# Sch.net
KiCad netlist of a schematic drawn in Altium Designer
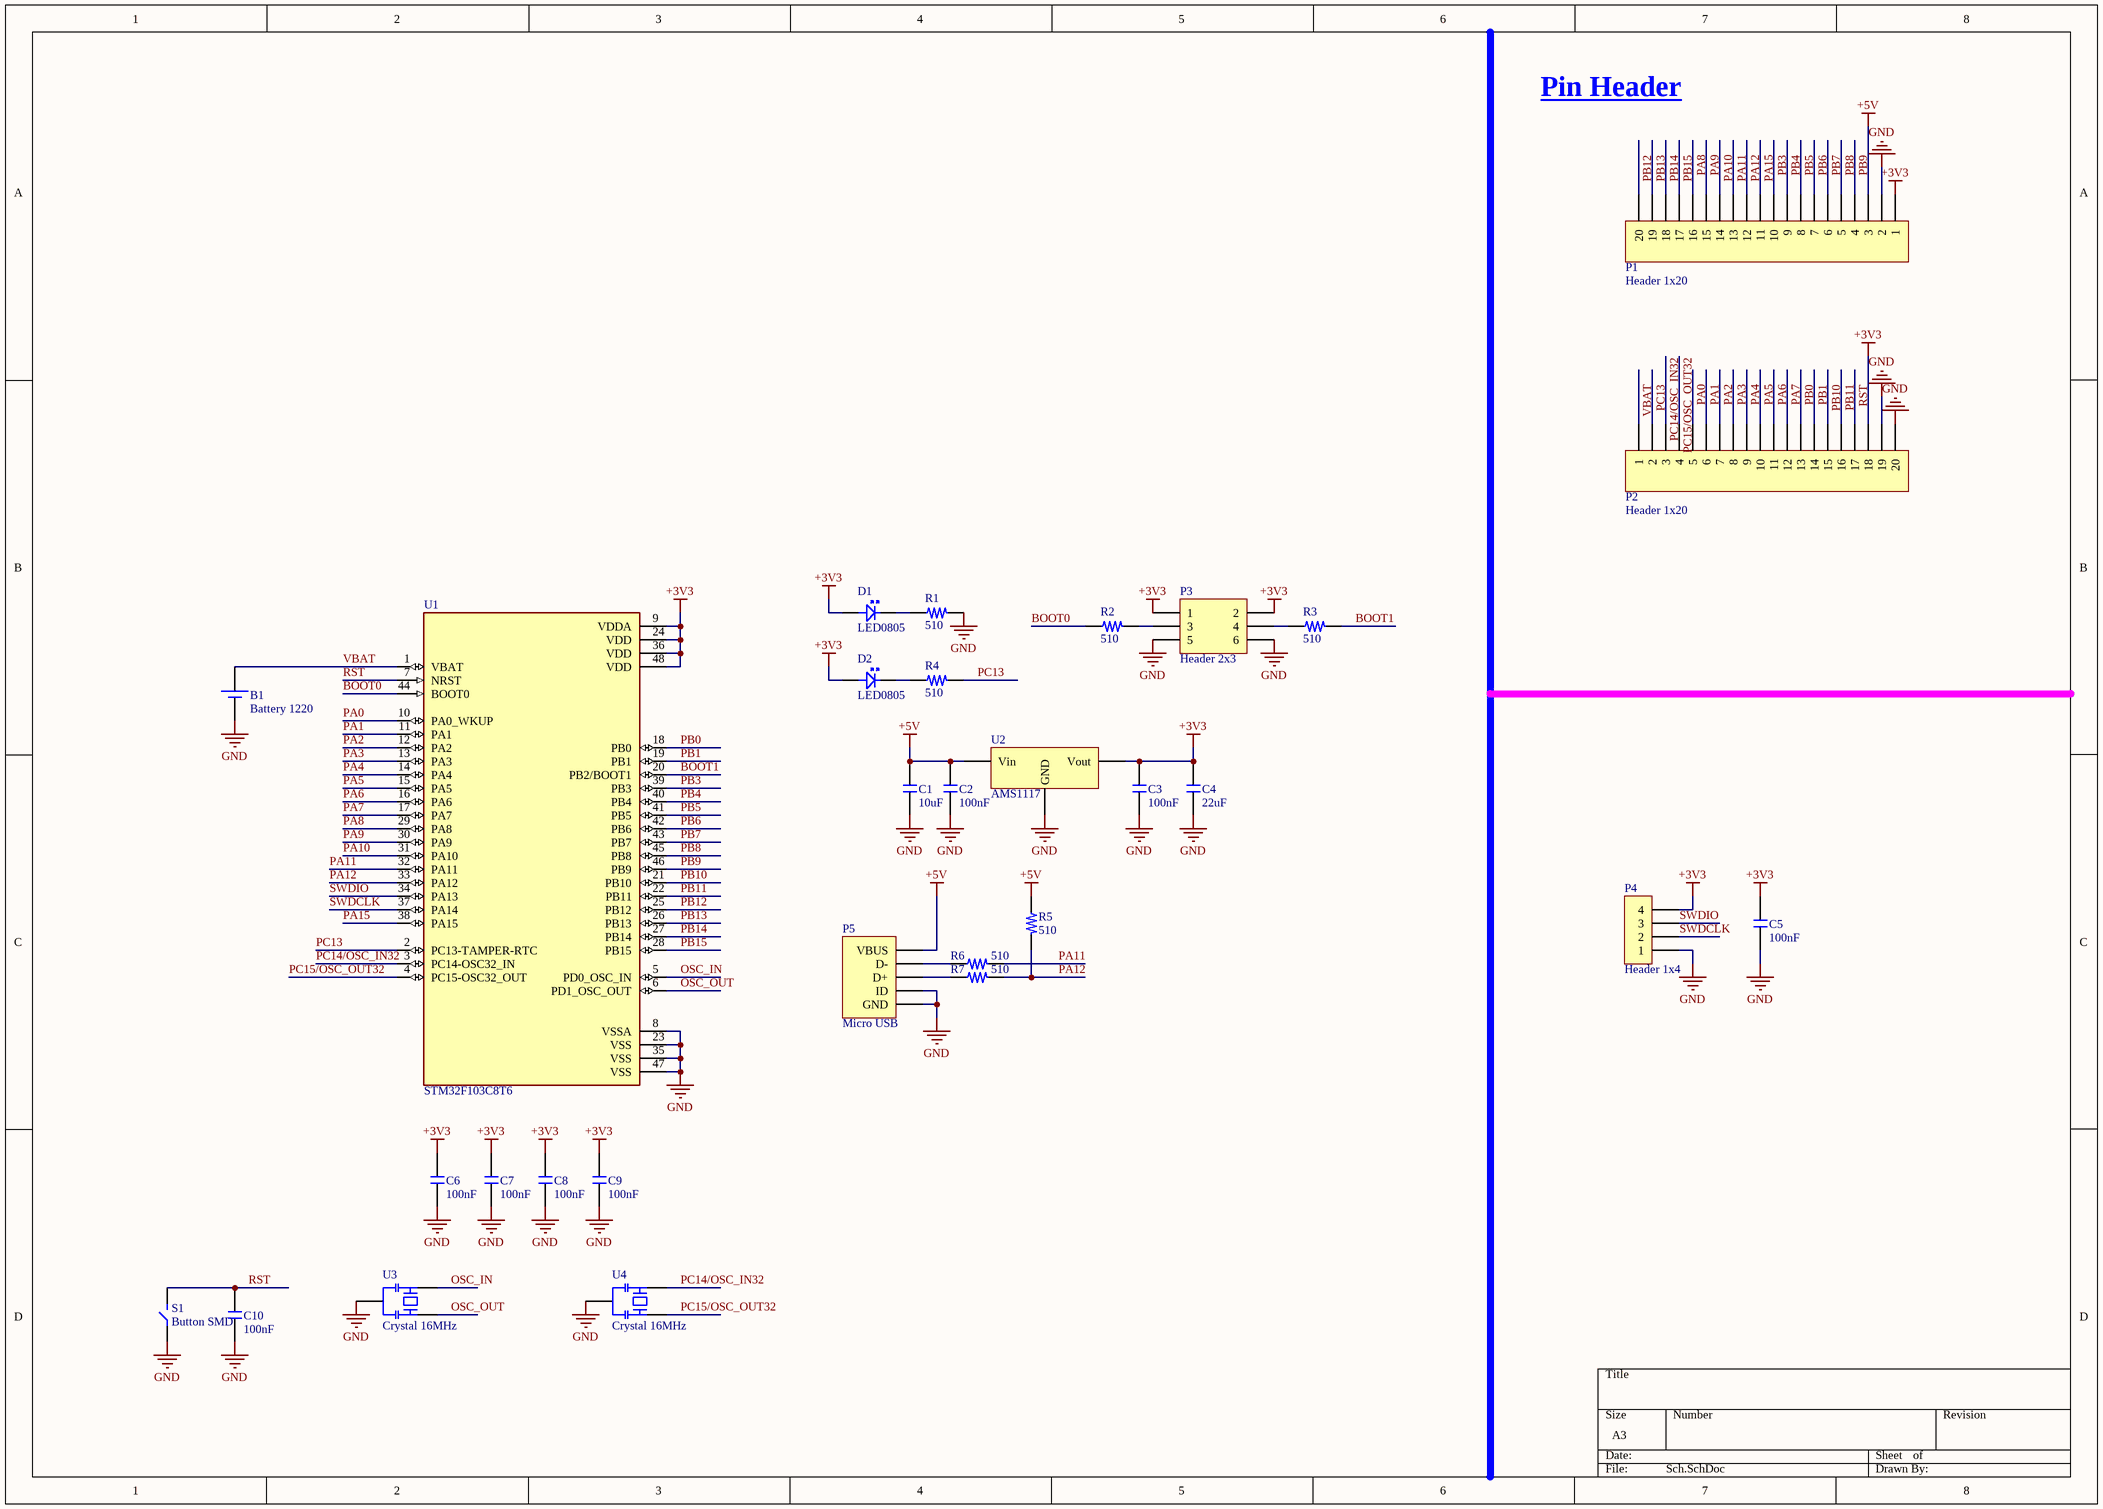
[diagram p0: Sch.SchDoc]

(export (version "E")
  (design (tool "Eeschema 10.0.6"))
  (components
    (comp (ref "B1")
      (value "Battery 1220")
      (footprint "Battery 1220")
      (libsource (lib "Custom_Sch") (part "Battery 1220"))
    )
    (comp (ref "C1") (value "10uF") (footprint "C805") (libsource (lib "Custom_Sch") (part "C0805")))
    (comp (ref "C2") (value "100nF") (footprint "C805") (libsource (lib "Custom_Sch") (part "C0805")))
    (comp (ref "C3") (value "100nF") (footprint "C805") (libsource (lib "Custom_Sch") (part "C0805")))
    (comp (ref "C4") (value "22uF") (footprint "C805") (libsource (lib "Custom_Sch") (part "C0805")))
    (comp (ref "C5") (value "100nF") (footprint "C805") (libsource (lib "Custom_Sch") (part "C0805")))
    (comp (ref "C6") (value "100nF") (footprint "C805") (libsource (lib "Custom_Sch") (part "C0805")))
    (comp (ref "C7") (value "100nF") (footprint "C805") (libsource (lib "Custom_Sch") (part "C0805")))
    (comp (ref "C8") (value "100nF") (footprint "C805") (libsource (lib "Custom_Sch") (part "C0805")))
    (comp (ref "C9") (value "100nF") (footprint "C805") (libsource (lib "Custom_Sch") (part "C0805")))
    (comp (ref "C10") (value "100nF") (footprint "C805") (libsource (lib "Custom_Sch") (part "C0805")))
    (comp (ref "D1") (value "LED0805") (footprint "LED0805") (libsource (lib "Custom_Sch") (part "LED0805")))
    (comp (ref "D2") (value "LED0805") (footprint "LED0805") (libsource (lib "Custom_Sch") (part "LED0805")))
    (comp (ref "P1")
      (value "Header 1x20")
      (footprint "Header 1x20")
      (libsource (lib "") (part "Header 1x20_1"))
    )
    (comp (ref "P2")
      (value "Header 1x20")
      (footprint "Header 1x20")
      (libsource (lib "Custom_Sch") (part "Header 1x20"))
    )
    (comp (ref "P3")
      (value "Header 2x3")
      (footprint "Header 2x3")
      (libsource (lib "Custom_Sch") (part "Header 2x3"))
    )
    (comp (ref "P4")
      (value "Header 1x4")
      (footprint "Header 1x4")
      (libsource (lib "Custom_Sch") (part "Header 1x4"))
    )
    (comp (ref "P5")
      (value "Micro USB")
      (footprint "Micro USB")
      (libsource (lib "Custom_Sch") (part "Micro USB"))
    )
    (comp (ref "R1") (value "510") (footprint "R805") (libsource (lib "Custom_Sch") (part "R0805")))
    (comp (ref "R2") (value "510") (footprint "R805") (libsource (lib "Custom_Sch") (part "R0805")))
    (comp (ref "R3") (value "510") (footprint "R805") (libsource (lib "Custom_Sch") (part "R0805")))
    (comp (ref "R4") (value "510") (footprint "R805") (libsource (lib "Custom_Sch") (part "R0805")))
    (comp (ref "R5") (value "510") (footprint "R805") (libsource (lib "Custom_Sch") (part "R0805")))
    (comp (ref "R6") (value "510") (footprint "R805") (libsource (lib "Custom_Sch") (part "R0805")))
    (comp (ref "R7") (value "510") (footprint "R805") (libsource (lib "Custom_Sch") (part "R0805")))
    (comp (ref "S1")
      (value "Button SMD")
      (footprint "Button SMD")
      (libsource (lib "Custom_Sch") (part "Button SMD"))
    )
    (comp (ref "U1")
      (value "STM32F103C8T6")
      (footprint "QFP50P900X900X160-48N")
      (description "ARMÂ® CortexÂ®-M3 STM32F1 Microcontroller IC 32-Bit 72MHz 64KB _64K x 8_ FLASH")
      (fields (field (name "MF") "STMicroelectronics"))
      (libsource (lib "Sch_Lib") (part "STM32F103C8T6"))
    )
    (comp (ref "U2") (value "AMS1117") (footprint "SOT223") (libsource (lib "Custom_Sch") (part "AMS1117")))
    (comp (ref "U3")
      (value "Crystal 16MHz")
      (footprint "Crystal 16MHz")
      (libsource (lib "Project_LIB") (part "Crystal 16MHz"))
    )
    (comp (ref "U4")
      (value "Crystal 16MHz")
      (footprint "Crystal 16MHz")
      (libsource (lib "Project_LIB") (part "Crystal 16MHz"))
    )
  )
  (nets
    (net (code "1") (name "+3V3") (class "Default")
      (node (ref "C3") (pin "2") (pinfunction "2_2") (pintype "passive"))
      (node (ref "C4") (pin "2") (pinfunction "2_2") (pintype "passive"))
      (node (ref "C5") (pin "2") (pinfunction "2_2") (pintype "passive"))
      (node (ref "C6") (pin "2") (pinfunction "2_2") (pintype "passive"))
      (node (ref "C7") (pin "2") (pinfunction "2_2") (pintype "passive"))
      (node (ref "C8") (pin "2") (pinfunction "2_2") (pintype "passive"))
      (node (ref "C9") (pin "2") (pinfunction "2_2") (pintype "passive"))
      (node (ref "D1") (pin "1") (pinfunction "1_1") (pintype "passive"))
      (node (ref "D2") (pin "1") (pinfunction "1_1") (pintype "passive"))
      (node (ref "P1") (pin "1") (pinfunction "1_1") (pintype "passive"))
      (node (ref "P2") (pin "18") (pinfunction "18_18") (pintype "passive"))
      (node (ref "P3") (pin "1") (pinfunction "1_1") (pintype "passive"))
      (node (ref "P3") (pin "2") (pinfunction "2_2") (pintype "passive"))
      (node (ref "P4") (pin "4") (pinfunction "4_4") (pintype "passive"))
      (node (ref "U1") (pin "24") (pinfunction "VDD_24") (pintype "power_in"))
      (node (ref "U1") (pin "36") (pinfunction "VDD_36") (pintype "power_in"))
      (node (ref "U1") (pin "48") (pinfunction "VDD_48") (pintype "power_in"))
      (node (ref "U1") (pin "9") (pinfunction "VDDA_9") (pintype "power_in"))
      (node (ref "U2") (pin "2") (pinfunction "Vout_2") (pintype "passive"))
    )
    (net (code "2") (name "+5V") (class "Default")
      (node (ref "C1") (pin "2") (pinfunction "2_2") (pintype "passive"))
      (node (ref "C2") (pin "2") (pinfunction "2_2") (pintype "passive"))
      (node (ref "P1") (pin "3") (pinfunction "3_3") (pintype "passive"))
      (node (ref "P5") (pin "1") (pinfunction "VBUS_1") (pintype "passive"))
      (node (ref "R5") (pin "1") (pinfunction "1_1") (pintype "passive"))
      (node (ref "U2") (pin "3") (pinfunction "Vin_3") (pintype "passive"))
    )
    (net (code "3") (name "/BOOT0") (class "Default")
      (node (ref "R2") (pin "1") (pinfunction "1_1") (pintype "passive"))
      (node (ref "U1") (pin "44") (pinfunction "BOOT0_44") (pintype "input"))
    )
    (net (code "4") (name "/BOOT1") (class "Default")
      (node (ref "R3") (pin "2") (pinfunction "2_2") (pintype "passive"))
      (node (ref "U1") (pin "20") (pinfunction "PB2/BOOT1_20") (pintype "bidirectional"))
    )
    (net (code "5") (name "/OSC_IN") (class "Default")
      (node (ref "U1") (pin "5") (pinfunction "PD0_OSC_IN_5") (pintype "bidirectional"))
      (node (ref "U3") (pin "1") (pinfunction "1_1") (pintype "passive"))
    )
    (net (code "6") (name "/OSC_OUT") (class "Default")
      (node (ref "U1") (pin "6") (pinfunction "PD1_OSC_OUT_6") (pintype "bidirectional"))
      (node (ref "U3") (pin "3") (pinfunction "3_3") (pintype "passive"))
    )
    (net (code "7") (name "/PA0") (class "Default")
      (node (ref "P2") (pin "5") (pinfunction "5_5") (pintype "passive"))
      (node (ref "U1") (pin "10") (pinfunction "PA0_WKUP_10") (pintype "bidirectional"))
    )
    (net (code "8") (name "/PA1") (class "Default")
      (node (ref "P2") (pin "6") (pinfunction "6_6") (pintype "passive"))
      (node (ref "U1") (pin "11") (pinfunction "PA1_11") (pintype "bidirectional"))
    )
    (net (code "9") (name "/PA2") (class "Default")
      (node (ref "P2") (pin "7") (pinfunction "7_7") (pintype "passive"))
      (node (ref "U1") (pin "12") (pinfunction "PA2_12") (pintype "bidirectional"))
    )
    (net (code "10") (name "/PA3") (class "Default")
      (node (ref "P2") (pin "8") (pinfunction "8_8") (pintype "passive"))
      (node (ref "U1") (pin "13") (pinfunction "PA3_13") (pintype "bidirectional"))
    )
    (net (code "11") (name "/PA4") (class "Default")
      (node (ref "P2") (pin "9") (pinfunction "9_9") (pintype "passive"))
      (node (ref "U1") (pin "14") (pinfunction "PA4_14") (pintype "bidirectional"))
    )
    (net (code "12") (name "/PA5") (class "Default")
      (node (ref "P2") (pin "10") (pinfunction "10_10") (pintype "passive"))
      (node (ref "U1") (pin "15") (pinfunction "PA5_15") (pintype "bidirectional"))
    )
    (net (code "13") (name "/PA6") (class "Default")
      (node (ref "P2") (pin "11") (pinfunction "11_11") (pintype "passive"))
      (node (ref "U1") (pin "16") (pinfunction "PA6_16") (pintype "bidirectional"))
    )
    (net (code "14") (name "/PA7") (class "Default")
      (node (ref "P2") (pin "12") (pinfunction "12_12") (pintype "passive"))
      (node (ref "U1") (pin "17") (pinfunction "PA7_17") (pintype "bidirectional"))
    )
    (net (code "15") (name "/PA8") (class "Default")
      (node (ref "P1") (pin "16") (pinfunction "16_16") (pintype "passive"))
      (node (ref "U1") (pin "29") (pinfunction "PA8_29") (pintype "bidirectional"))
    )
    (net (code "16") (name "/PA9") (class "Default")
      (node (ref "P1") (pin "15") (pinfunction "15_15") (pintype "passive"))
      (node (ref "U1") (pin "30") (pinfunction "PA9_30") (pintype "bidirectional"))
    )
    (net (code "17") (name "/PA10") (class "Default")
      (node (ref "P1") (pin "14") (pinfunction "14_14") (pintype "passive"))
      (node (ref "U1") (pin "31") (pinfunction "PA10_31") (pintype "bidirectional"))
    )
    (net (code "18") (name "/PA11") (class "Default")
      (node (ref "P1") (pin "13") (pinfunction "13_13") (pintype "passive"))
      (node (ref "R6") (pin "2") (pinfunction "2_2") (pintype "passive"))
      (node (ref "U1") (pin "32") (pinfunction "PA11_32") (pintype "bidirectional"))
    )
    (net (code "19") (name "/PA12") (class "Default")
      (node (ref "P1") (pin "12") (pinfunction "12_12") (pintype "passive"))
      (node (ref "R5") (pin "2") (pinfunction "2_2") (pintype "passive"))
      (node (ref "R7") (pin "2") (pinfunction "2_2") (pintype "passive"))
      (node (ref "U1") (pin "33") (pinfunction "PA12_33") (pintype "bidirectional"))
    )
    (net (code "20") (name "/PA15") (class "Default")
      (node (ref "P1") (pin "11") (pinfunction "11_11") (pintype "passive"))
      (node (ref "U1") (pin "38") (pinfunction "PA15_38") (pintype "bidirectional"))
    )
    (net (code "21") (name "/PB0") (class "Default")
      (node (ref "P2") (pin "13") (pinfunction "13_13") (pintype "passive"))
      (node (ref "U1") (pin "18") (pinfunction "PB0_18") (pintype "bidirectional"))
    )
    (net (code "22") (name "/PB1") (class "Default")
      (node (ref "P2") (pin "14") (pinfunction "14_14") (pintype "passive"))
      (node (ref "U1") (pin "19") (pinfunction "PB1_19") (pintype "bidirectional"))
    )
    (net (code "23") (name "/PB3") (class "Default")
      (node (ref "P1") (pin "10") (pinfunction "10_10") (pintype "passive"))
      (node (ref "U1") (pin "39") (pinfunction "PB3_39") (pintype "bidirectional"))
    )
    (net (code "24") (name "/PB4") (class "Default")
      (node (ref "P1") (pin "9") (pinfunction "9_9") (pintype "passive"))
      (node (ref "U1") (pin "40") (pinfunction "PB4_40") (pintype "bidirectional"))
    )
    (net (code "25") (name "/PB5") (class "Default")
      (node (ref "P1") (pin "8") (pinfunction "8_8") (pintype "passive"))
      (node (ref "U1") (pin "41") (pinfunction "PB5_41") (pintype "bidirectional"))
    )
    (net (code "26") (name "/PB6") (class "Default")
      (node (ref "P1") (pin "7") (pinfunction "7_7") (pintype "passive"))
      (node (ref "U1") (pin "42") (pinfunction "PB6_42") (pintype "bidirectional"))
    )
    (net (code "27") (name "/PB7") (class "Default")
      (node (ref "P1") (pin "6") (pinfunction "6_6") (pintype "passive"))
      (node (ref "U1") (pin "43") (pinfunction "PB7_43") (pintype "bidirectional"))
    )
    (net (code "28") (name "/PB8") (class "Default")
      (node (ref "P1") (pin "5") (pinfunction "5_5") (pintype "passive"))
      (node (ref "U1") (pin "45") (pinfunction "PB8_45") (pintype "bidirectional"))
    )
    (net (code "29") (name "/PB9") (class "Default")
      (node (ref "P1") (pin "4") (pinfunction "4_4") (pintype "passive"))
      (node (ref "U1") (pin "46") (pinfunction "PB9_46") (pintype "bidirectional"))
    )
    (net (code "30") (name "/PB10") (class "Default")
      (node (ref "P2") (pin "15") (pinfunction "15_15") (pintype "passive"))
      (node (ref "U1") (pin "21") (pinfunction "PB10_21") (pintype "bidirectional"))
    )
    (net (code "31") (name "/PB11") (class "Default")
      (node (ref "P2") (pin "16") (pinfunction "16_16") (pintype "passive"))
      (node (ref "U1") (pin "22") (pinfunction "PB11_22") (pintype "bidirectional"))
    )
    (net (code "32") (name "/PB12") (class "Default")
      (node (ref "P1") (pin "20") (pinfunction "20_20") (pintype "passive"))
      (node (ref "U1") (pin "25") (pinfunction "PB12_25") (pintype "bidirectional"))
    )
    (net (code "33") (name "/PB13") (class "Default")
      (node (ref "P1") (pin "19") (pinfunction "19_19") (pintype "passive"))
      (node (ref "U1") (pin "26") (pinfunction "PB13_26") (pintype "bidirectional"))
    )
    (net (code "34") (name "/PB14") (class "Default")
      (node (ref "P1") (pin "18") (pinfunction "18_18") (pintype "passive"))
      (node (ref "U1") (pin "27") (pinfunction "PB14_27") (pintype "bidirectional"))
    )
    (net (code "35") (name "/PB15") (class "Default")
      (node (ref "P1") (pin "17") (pinfunction "17_17") (pintype "passive"))
      (node (ref "U1") (pin "28") (pinfunction "PB15_28") (pintype "bidirectional"))
    )
    (net (code "36") (name "/PC13") (class "Default")
      (node (ref "P2") (pin "2") (pinfunction "2_2") (pintype "passive"))
      (node (ref "R4") (pin "2") (pinfunction "2_2") (pintype "passive"))
      (node (ref "U1") (pin "2") (pinfunction "PC13-TAMPER-RTC_2") (pintype "bidirectional"))
    )
    (net (code "37") (name "/PC14{slash}OSC_IN32") (class "Default")
      (node (ref "P2") (pin "3") (pinfunction "3_3") (pintype "passive"))
      (node (ref "U1") (pin "3") (pinfunction "PC14-OSC32_IN_3") (pintype "bidirectional"))
      (node (ref "U4") (pin "1") (pinfunction "1_1") (pintype "passive"))
    )
    (net (code "38") (name "/PC15{slash}OSC_OUT32") (class "Default")
      (node (ref "P2") (pin "4") (pinfunction "4_4") (pintype "passive"))
      (node (ref "U1") (pin "4") (pinfunction "PC15-OSC32_OUT_4") (pintype "bidirectional"))
      (node (ref "U4") (pin "3") (pinfunction "3_3") (pintype "passive"))
    )
    (net (code "39") (name "/RST") (class "Default")
      (node (ref "C10") (pin "2") (pinfunction "2_2") (pintype "passive"))
      (node (ref "P2") (pin "17") (pinfunction "17_17") (pintype "passive"))
      (node (ref "S1") (pin "2") (pinfunction "2_2") (pintype "passive"))
      (node (ref "U1") (pin "7") (pinfunction "NRST_7") (pintype "input"))
    )
    (net (code "40") (name "/SWDCLK") (class "Default")
      (node (ref "P4") (pin "2") (pinfunction "2_2") (pintype "passive"))
      (node (ref "U1") (pin "37") (pinfunction "PA14_37") (pintype "bidirectional"))
    )
    (net (code "41") (name "/SWDIO") (class "Default")
      (node (ref "P4") (pin "3") (pinfunction "3_3") (pintype "passive"))
      (node (ref "U1") (pin "34") (pinfunction "PA13_34") (pintype "bidirectional"))
    )
    (net (code "42") (name "/VBAT") (class "Default")
      (node (ref "B1") (pin "2") (pinfunction "2_2") (pintype "passive"))
      (node (ref "P2") (pin "1") (pinfunction "1_1") (pintype "passive"))
      (node (ref "U1") (pin "1") (pinfunction "VBAT_1") (pintype "bidirectional"))
    )
    (net (code "43") (name "GND") (class "Default")
      (node (ref "B1") (pin "1") (pinfunction "1_1") (pintype "passive"))
      (node (ref "C1") (pin "1") (pinfunction "1_1") (pintype "passive"))
      (node (ref "C10") (pin "1") (pinfunction "1_1") (pintype "passive"))
      (node (ref "C2") (pin "1") (pinfunction "1_1") (pintype "passive"))
      (node (ref "C3") (pin "1") (pinfunction "1_1") (pintype "passive"))
      (node (ref "C4") (pin "1") (pinfunction "1_1") (pintype "passive"))
      (node (ref "C5") (pin "1") (pinfunction "1_1") (pintype "passive"))
      (node (ref "C6") (pin "1") (pinfunction "1_1") (pintype "passive"))
      (node (ref "C7") (pin "1") (pinfunction "1_1") (pintype "passive"))
      (node (ref "C8") (pin "1") (pinfunction "1_1") (pintype "passive"))
      (node (ref "C9") (pin "1") (pinfunction "1_1") (pintype "passive"))
      (node (ref "P1") (pin "2") (pinfunction "2_2") (pintype "passive"))
      (node (ref "P2") (pin "19") (pinfunction "19_19") (pintype "passive"))
      (node (ref "P2") (pin "20") (pinfunction "20_20") (pintype "passive"))
      (node (ref "P3") (pin "5") (pinfunction "5_5") (pintype "passive"))
      (node (ref "P3") (pin "6") (pinfunction "6_6") (pintype "passive"))
      (node (ref "P4") (pin "1") (pinfunction "1_1") (pintype "passive"))
      (node (ref "P5") (pin "4") (pinfunction "ID_4") (pintype "passive"))
      (node (ref "P5") (pin "5") (pinfunction "GND_5") (pintype "passive"))
      (node (ref "R1") (pin "2") (pinfunction "2_2") (pintype "passive"))
      (node (ref "S1") (pin "1") (pinfunction "1_1") (pintype "passive"))
      (node (ref "U1") (pin "23") (pinfunction "VSS_23") (pintype "power_in"))
      (node (ref "U1") (pin "35") (pinfunction "VSS_35") (pintype "power_in"))
      (node (ref "U1") (pin "47") (pinfunction "VSS_47") (pintype "power_in"))
      (node (ref "U1") (pin "8") (pinfunction "VSSA_8") (pintype "power_in"))
      (node (ref "U2") (pin "1") (pinfunction "GND_1") (pintype "passive"))
      (node (ref "U3") (pin "2") (pinfunction "2_2") (pintype "passive"))
      (node (ref "U4") (pin "2") (pinfunction "2_2") (pintype "passive"))
    )
    (net (code "44") (name "Net-(D1-Pad2)") (class "Default")
      (node (ref "D1") (pin "2") (pinfunction "2_2") (pintype "passive"))
      (node (ref "R1") (pin "1") (pinfunction "1_1") (pintype "passive"))
    )
    (net (code "45") (name "Net-(D2-Pad2)") (class "Default")
      (node (ref "D2") (pin "2") (pinfunction "2_2") (pintype "passive"))
      (node (ref "R4") (pin "1") (pinfunction "1_1") (pintype "passive"))
    )
    (net (code "46") (name "Net-(P3-Pad3)") (class "Default")
      (node (ref "P3") (pin "3") (pinfunction "3_3") (pintype "passive"))
      (node (ref "R2") (pin "2") (pinfunction "2_2") (pintype "passive"))
    )
    (net (code "47") (name "Net-(P3-Pad4)") (class "Default")
      (node (ref "P3") (pin "4") (pinfunction "4_4") (pintype "passive"))
      (node (ref "R3") (pin "1") (pinfunction "1_1") (pintype "passive"))
    )
    (net (code "48") (name "Net-(P5-D+)") (class "Default")
      (node (ref "P5") (pin "3") (pinfunction "D+_3") (pintype "passive"))
      (node (ref "R7") (pin "1") (pinfunction "1_1") (pintype "passive"))
    )
    (net (code "49") (name "Net-(P5-D-)") (class "Default")
      (node (ref "P5") (pin "2") (pinfunction "D-_2") (pintype "passive"))
      (node (ref "R6") (pin "1") (pinfunction "1_1") (pintype "passive"))
    )
  )
)
